# IMU.net
KiCad netlist of a schematic drawn in EAGLE
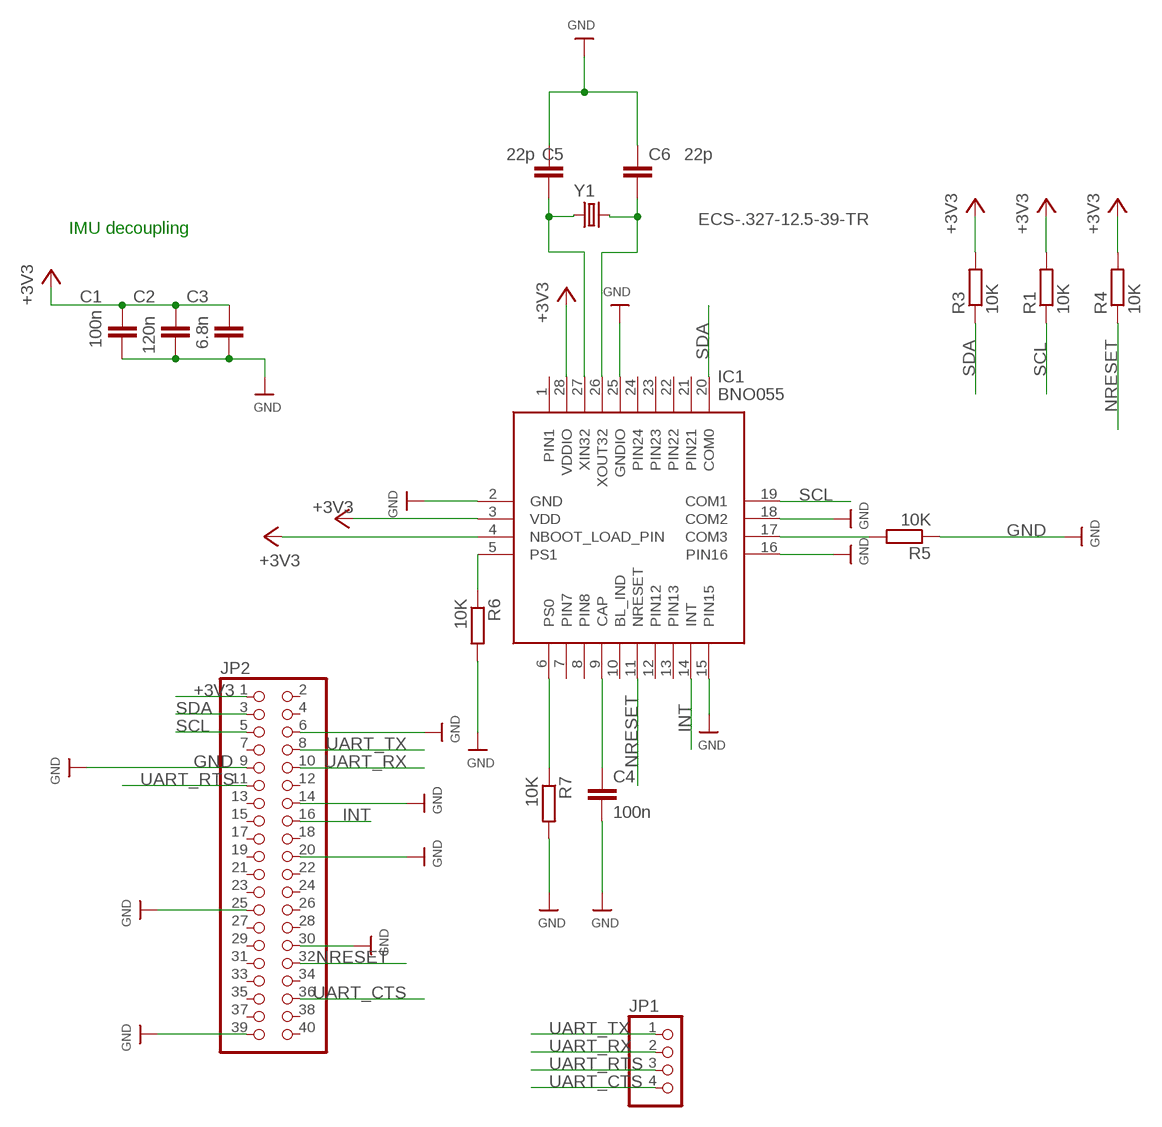
[diagram p0: schematic, sheet 1]

(export (version "E")
  (design (tool "Eeschema 10.0.6"))
  (components
    (comp (ref "C1")
      (value "100n")
      (footprint "eagle-import:C0805")
      (libsource (lib "eagle-import") (part "C-EUC0805"))
    )
    (comp (ref "C2")
      (value "120n")
      (footprint "eagle-import:C0805")
      (libsource (lib "eagle-import") (part "C-EUC0805"))
    )
    (comp (ref "C3")
      (value "6.8n")
      (footprint "eagle-import:C0805")
      (libsource (lib "eagle-import") (part "C-EUC0805"))
    )
    (comp (ref "C4")
      (value "100n")
      (footprint "eagle-import:C0805")
      (libsource (lib "eagle-import") (part "C-EUC0805"))
    )
    (comp (ref "C5")
      (value "22p")
      (footprint "eagle-import:C0805")
      (libsource (lib "eagle-import") (part "C-EUC0805"))
    )
    (comp (ref "C6")
      (value "22p")
      (footprint "eagle-import:C0805")
      (libsource (lib "eagle-import") (part "C-EUC0805"))
    )
    (comp (ref "IC1")
      (value "BNO055")
      (footprint "eagle-import:BNO055")
      (fields (field (name "MOUSER_PART_NUMBER") "262-BNO055"))
      (libsource (lib "eagle-import") (part "BNO055"))
    )
    (comp (ref "JP1")
      (value "PINHD-1X4")
      (footprint "eagle-import:1X04")
      (libsource (lib "eagle-import") (part "PINHD-1X4"))
    )
    (comp (ref "JP2")
      (value "PINHD-2X20")
      (footprint "eagle-import:2X20")
      (libsource (lib "eagle-import") (part "PINHD-2X20"))
    )
    (comp (ref "R1")
      (value "10K")
      (footprint "eagle-import:R0805")
      (libsource (lib "eagle-import") (part "R-EU_R0805"))
    )
    (comp (ref "R3")
      (value "10K")
      (footprint "eagle-import:R0805")
      (libsource (lib "eagle-import") (part "R-EU_R0805"))
    )
    (comp (ref "R4")
      (value "10K")
      (footprint "eagle-import:R0805")
      (libsource (lib "eagle-import") (part "R-EU_R0805"))
    )
    (comp (ref "R5")
      (value "10K")
      (footprint "eagle-import:R0805")
      (libsource (lib "eagle-import") (part "R-EU_R0805"))
    )
    (comp (ref "R6")
      (value "10K")
      (footprint "eagle-import:R0805")
      (libsource (lib "eagle-import") (part "R-EU_R0805"))
    )
    (comp (ref "R7")
      (value "10K")
      (footprint "eagle-import:R0805")
      (libsource (lib "eagle-import") (part "R-EU_R0805"))
    )
    (comp (ref "Y1")
      (value "ECS-.327-12.5-39-TR")
      (footprint "eagle-import:ECS-.327-12.5-39-TR")
      (fields
        (field (name "DIGIKEY_PART_NUMBER") "XC1658TR-ND")
        (field (name "MANUFACTURER") "ECS Inc.")
        (field (name "CREATED_BY") "PCBLayout.com")
      )
      (libsource (lib "eagle-import") (part "ECS-.327-12.5-39-TR"))
    )
  )
  (nets
    (net (code "1") (name "+3V3") (class "Default")
      (node (ref "C1") (pin "1") (pinfunction "1_1") (pintype "passive"))
      (node (ref "C2") (pin "1") (pinfunction "1_1") (pintype "passive"))
      (node (ref "C3") (pin "1") (pinfunction "1_1") (pintype "passive"))
      (node (ref "IC1") (pin "28") (pinfunction "VDDIO_28") (pintype "input"))
      (node (ref "IC1") (pin "3") (pinfunction "VDD_3") (pintype "power_in"))
      (node (ref "IC1") (pin "4") (pinfunction "NBOOT_LOAD_PIN_4") (pintype "power_in"))
      (node (ref "JP2") (pin "1") (pinfunction "1_1") (pintype "passive"))
      (node (ref "R1") (pin "2") (pinfunction "2_2") (pintype "passive"))
      (node (ref "R3") (pin "2") (pinfunction "2_2") (pintype "passive"))
      (node (ref "R4") (pin "2") (pinfunction "2_2") (pintype "passive"))
    )
    (net (code "2") (name "/INT") (class "Default")
      (node (ref "IC1") (pin "14") (pinfunction "INT_14") (pintype "bidirectional"))
      (node (ref "JP2") (pin "16") (pinfunction "16_16") (pintype "passive"))
    )
    (net (code "3") (name "/NRESET") (class "Default")
      (node (ref "IC1") (pin "11") (pinfunction "NRESET_11") (pintype "input"))
      (node (ref "JP2") (pin "32") (pinfunction "32_32") (pintype "passive"))
      (node (ref "R4") (pin "1") (pinfunction "1_1") (pintype "passive"))
    )
    (net (code "4") (name "/SCL") (class "Default")
      (node (ref "IC1") (pin "19") (pinfunction "COM1_19") (pintype "input"))
      (node (ref "JP2") (pin "5") (pinfunction "5_5") (pintype "passive"))
      (node (ref "R1") (pin "1") (pinfunction "1_1") (pintype "passive"))
    )
    (net (code "5") (name "/SDA") (class "Default")
      (node (ref "IC1") (pin "20") (pinfunction "COM0_20") (pintype "bidirectional"))
      (node (ref "JP2") (pin "3") (pinfunction "3_3") (pintype "passive"))
      (node (ref "R3") (pin "1") (pinfunction "1_1") (pintype "passive"))
    )
    (net (code "6") (name "/UART_CTS") (class "Default")
      (node (ref "JP1") (pin "4") (pinfunction "4_4") (pintype "passive"))
      (node (ref "JP2") (pin "36") (pinfunction "36_36") (pintype "passive"))
    )
    (net (code "7") (name "/UART_RTS") (class "Default")
      (node (ref "JP1") (pin "3") (pinfunction "3_3") (pintype "passive"))
      (node (ref "JP2") (pin "11") (pinfunction "11_11") (pintype "passive"))
    )
    (net (code "8") (name "/UART_RX") (class "Default")
      (node (ref "JP1") (pin "2") (pinfunction "2_2") (pintype "passive"))
      (node (ref "JP2") (pin "10") (pinfunction "10_10") (pintype "passive"))
    )
    (net (code "9") (name "/UART_TX") (class "Default")
      (node (ref "JP1") (pin "1") (pinfunction "1_1") (pintype "passive"))
      (node (ref "JP2") (pin "8") (pinfunction "8_8") (pintype "passive"))
    )
    (net (code "10") (name "GND") (class "Default")
      (node (ref "C1") (pin "2") (pinfunction "2_2") (pintype "passive"))
      (node (ref "C2") (pin "2") (pinfunction "2_2") (pintype "passive"))
      (node (ref "C3") (pin "2") (pinfunction "2_2") (pintype "passive"))
      (node (ref "C4") (pin "2") (pinfunction "2_2") (pintype "passive"))
      (node (ref "C5") (pin "1") (pinfunction "1_1") (pintype "passive"))
      (node (ref "C6") (pin "1") (pinfunction "1_1") (pintype "passive"))
      (node (ref "IC1") (pin "15") (pinfunction "PIN15_15") (pintype "bidirectional"))
      (node (ref "IC1") (pin "16") (pinfunction "PIN16_16") (pintype "bidirectional"))
      (node (ref "IC1") (pin "18") (pinfunction "COM2_18") (pintype "input"))
      (node (ref "IC1") (pin "2") (pinfunction "GND_2") (pintype "input"))
      (node (ref "IC1") (pin "25") (pinfunction "GNDIO_25") (pintype "bidirectional"))
      (node (ref "JP2") (pin "14") (pinfunction "14_14") (pintype "passive"))
      (node (ref "JP2") (pin "20") (pinfunction "20_20") (pintype "passive"))
      (node (ref "JP2") (pin "25") (pinfunction "25_25") (pintype "passive"))
      (node (ref "JP2") (pin "30") (pinfunction "30_30") (pintype "passive"))
      (node (ref "JP2") (pin "39") (pinfunction "39_39") (pintype "passive"))
      (node (ref "JP2") (pin "6") (pinfunction "6_6") (pintype "passive"))
      (node (ref "JP2") (pin "9") (pinfunction "9_9") (pintype "passive"))
      (node (ref "R5") (pin "1") (pinfunction "1_1") (pintype "passive"))
      (node (ref "R6") (pin "2") (pinfunction "2_2") (pintype "passive"))
      (node (ref "R7") (pin "2") (pinfunction "2_2") (pintype "passive"))
    )
    (net (code "11") (name "Net-(IC1-CAP)") (class "Default")
      (node (ref "C4") (pin "1") (pinfunction "1_1") (pintype "passive"))
      (node (ref "IC1") (pin "9") (pinfunction "CAP_9") (pintype "power_in"))
    )
    (net (code "12") (name "Net-(IC1-COM3)") (class "Default")
      (node (ref "IC1") (pin "17") (pinfunction "COM3_17") (pintype "bidirectional"))
      (node (ref "R5") (pin "2") (pinfunction "2_2") (pintype "passive"))
    )
    (net (code "13") (name "Net-(IC1-PS0)") (class "Default")
      (node (ref "IC1") (pin "6") (pinfunction "PS0_6") (pintype "power_in"))
      (node (ref "R7") (pin "1") (pinfunction "1_1") (pintype "passive"))
    )
    (net (code "14") (name "Net-(IC1-PS1)") (class "Default")
      (node (ref "IC1") (pin "5") (pinfunction "PS1_5") (pintype "input"))
      (node (ref "R6") (pin "1") (pinfunction "1_1") (pintype "passive"))
    )
    (net (code "15") (name "Net-(IC1-XIN32)") (class "Default")
      (node (ref "C5") (pin "2") (pinfunction "2_2") (pintype "passive"))
      (node (ref "IC1") (pin "27") (pinfunction "XIN32_27") (pintype "bidirectional"))
      (node (ref "Y1") (pin "1") (pinfunction "1_1") (pintype "passive"))
    )
    (net (code "16") (name "Net-(IC1-XOUT32)") (class "Default")
      (node (ref "C6") (pin "2") (pinfunction "2_2") (pintype "passive"))
      (node (ref "IC1") (pin "26") (pinfunction "XOUT32_26") (pintype "input"))
      (node (ref "Y1") (pin "2") (pinfunction "2_2") (pintype "passive"))
    )
    (net (code "17") (name "unconnected-(IC1-BL_IND-Pad10)") (class "Default")
      (node (ref "IC1") (pin "10") (pinfunction "BL_IND_10") (pintype "input"))
    )
    (net (code "18") (name "unconnected-(IC1-PIN1-Pad1)") (class "Default")
      (node (ref "IC1") (pin "1") (pinfunction "PIN1_1") (pintype "input"))
    )
    (net (code "19") (name "unconnected-(IC1-PIN7-Pad7)") (class "Default")
      (node (ref "IC1") (pin "7") (pinfunction "PIN7_7") (pintype "input"))
    )
    (net (code "20") (name "unconnected-(IC1-PIN8-Pad8)") (class "Default")
      (node (ref "IC1") (pin "8") (pinfunction "PIN8_8") (pintype "output"))
    )
    (net (code "21") (name "unconnected-(IC1-PIN12-Pad12)") (class "Default")
      (node (ref "IC1") (pin "12") (pinfunction "PIN12_12") (pintype "input"))
    )
    (net (code "22") (name "unconnected-(IC1-PIN13-Pad13)") (class "Default")
      (node (ref "IC1") (pin "13") (pinfunction "PIN13_13") (pintype "input"))
    )
    (net (code "23") (name "unconnected-(IC1-PIN21-Pad21)") (class "Default")
      (node (ref "IC1") (pin "21") (pinfunction "PIN21_21") (pintype "bidirectional"))
    )
    (net (code "24") (name "unconnected-(IC1-PIN22-Pad22)") (class "Default")
      (node (ref "IC1") (pin "22") (pinfunction "PIN22_22") (pintype "input"))
    )
    (net (code "25") (name "unconnected-(IC1-PIN23-Pad23)") (class "Default")
      (node (ref "IC1") (pin "23") (pinfunction "PIN23_23") (pintype "input"))
    )
    (net (code "26") (name "unconnected-(IC1-PIN24-Pad24)") (class "Default")
      (node (ref "IC1") (pin "24") (pinfunction "PIN24_24") (pintype "input"))
    )
    (net (code "27") (name "unconnected-(JP2-Pad2)") (class "Default")
      (node (ref "JP2") (pin "2") (pinfunction "2_2") (pintype "passive"))
    )
    (net (code "28") (name "unconnected-(JP2-Pad4)") (class "Default")
      (node (ref "JP2") (pin "4") (pinfunction "4_4") (pintype "passive"))
    )
    (net (code "29") (name "unconnected-(JP2-Pad7)") (class "Default")
      (node (ref "JP2") (pin "7") (pinfunction "7_7") (pintype "passive"))
    )
    (net (code "30") (name "unconnected-(JP2-Pad12)") (class "Default")
      (node (ref "JP2") (pin "12") (pinfunction "12_12") (pintype "passive"))
    )
    (net (code "31") (name "unconnected-(JP2-Pad13)") (class "Default")
      (node (ref "JP2") (pin "13") (pinfunction "13_13") (pintype "passive"))
    )
    (net (code "32") (name "unconnected-(JP2-Pad15)") (class "Default")
      (node (ref "JP2") (pin "15") (pinfunction "15_15") (pintype "passive"))
    )
    (net (code "33") (name "unconnected-(JP2-Pad17)") (class "Default")
      (node (ref "JP2") (pin "17") (pinfunction "17_17") (pintype "passive"))
    )
    (net (code "34") (name "unconnected-(JP2-Pad18)") (class "Default")
      (node (ref "JP2") (pin "18") (pinfunction "18_18") (pintype "passive"))
    )
    (net (code "35") (name "unconnected-(JP2-Pad19)") (class "Default")
      (node (ref "JP2") (pin "19") (pinfunction "19_19") (pintype "passive"))
    )
    (net (code "36") (name "unconnected-(JP2-Pad21)") (class "Default")
      (node (ref "JP2") (pin "21") (pinfunction "21_21") (pintype "passive"))
    )
    (net (code "37") (name "unconnected-(JP2-Pad22)") (class "Default")
      (node (ref "JP2") (pin "22") (pinfunction "22_22") (pintype "passive"))
    )
    (net (code "38") (name "unconnected-(JP2-Pad23)") (class "Default")
      (node (ref "JP2") (pin "23") (pinfunction "23_23") (pintype "passive"))
    )
    (net (code "39") (name "unconnected-(JP2-Pad24)") (class "Default")
      (node (ref "JP2") (pin "24") (pinfunction "24_24") (pintype "passive"))
    )
    (net (code "40") (name "unconnected-(JP2-Pad26)") (class "Default")
      (node (ref "JP2") (pin "26") (pinfunction "26_26") (pintype "passive"))
    )
    (net (code "41") (name "unconnected-(JP2-Pad27)") (class "Default")
      (node (ref "JP2") (pin "27") (pinfunction "27_27") (pintype "passive"))
    )
    (net (code "42") (name "unconnected-(JP2-Pad28)") (class "Default")
      (node (ref "JP2") (pin "28") (pinfunction "28_28") (pintype "passive"))
    )
    (net (code "43") (name "unconnected-(JP2-Pad29)") (class "Default")
      (node (ref "JP2") (pin "29") (pinfunction "29_29") (pintype "passive"))
    )
    (net (code "44") (name "unconnected-(JP2-Pad31)") (class "Default")
      (node (ref "JP2") (pin "31") (pinfunction "31_31") (pintype "passive"))
    )
    (net (code "45") (name "unconnected-(JP2-Pad33)") (class "Default")
      (node (ref "JP2") (pin "33") (pinfunction "33_33") (pintype "passive"))
    )
    (net (code "46") (name "unconnected-(JP2-Pad34)") (class "Default")
      (node (ref "JP2") (pin "34") (pinfunction "34_34") (pintype "passive"))
    )
    (net (code "47") (name "unconnected-(JP2-Pad35)") (class "Default")
      (node (ref "JP2") (pin "35") (pinfunction "35_35") (pintype "passive"))
    )
    (net (code "48") (name "unconnected-(JP2-Pad37)") (class "Default")
      (node (ref "JP2") (pin "37") (pinfunction "37_37") (pintype "passive"))
    )
    (net (code "49") (name "unconnected-(JP2-Pad38)") (class "Default")
      (node (ref "JP2") (pin "38") (pinfunction "38_38") (pintype "passive"))
    )
    (net (code "50") (name "unconnected-(JP2-Pad40)") (class "Default")
      (node (ref "JP2") (pin "40") (pinfunction "40_40") (pintype "passive"))
    )
  )
)
